# MCU_newPins.net
KiCad netlist of a schematic drawn in Altium Designer
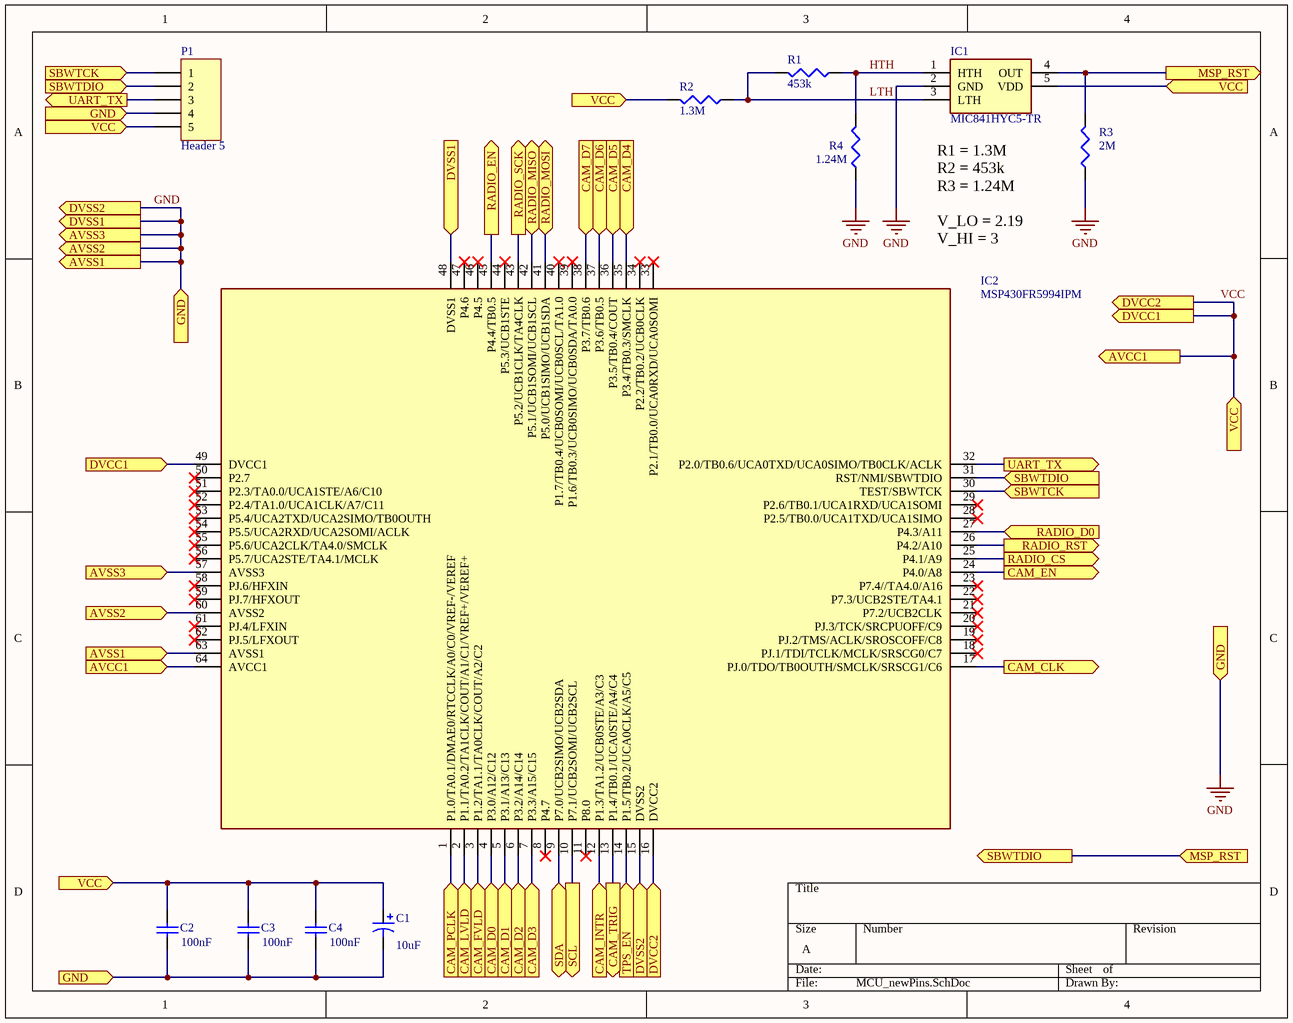
[diagram p0: MCU_newPins.SchDoc]

(export (version "E")
  (design (tool "Eeschema 10.0.6"))
  (components
    (comp (ref "C1")
      (value "10uF")
      (footprint "C1210")
      (description "Polarized Capacitor (Surface Mount)")
      (fields (field (name "PUBLISHER") "Altium Limited"))
      (libsource (lib "Miscellaneous Devices") (part "Cap Pol3"))
    )
    (comp (ref "C2")
      (value "100nF")
      (footprint "1608[0603]")
      (description "CAP CER 6.3V X5R/X7R 0603")
      (fields (field (name "Comment") "Cap") (field (name "PUBLISHER") "Altium Limited"))
      (libsource (lib "Miscellaneous Devices") (part "Cap"))
    )
    (comp (ref "C3")
      (value "100nF")
      (footprint "1608[0603]")
      (description "CAP CER 6.3V X5R/X7R 0603")
      (fields (field (name "Comment") "Cap") (field (name "PUBLISHER") "Altium Limited"))
      (libsource (lib "Miscellaneous Devices") (part "Cap"))
    )
    (comp (ref "C4")
      (value "100nF")
      (footprint "1608[0603]")
      (description "CAP CER 6.3V X5R/X7R 0603")
      (fields (field (name "Comment") "Cap") (field (name "PUBLISHER") "Altium Limited"))
      (libsource (lib "Miscellaneous Devices") (part "Cap"))
    )
    (comp (ref "IC1")
      (value "MIC841HYC5-TR")
      (footprint "SamacSys:SOT65P210X110-5N")
      (description "Comparator with 1.25% Reference and Adjustable Hysteresis")
      (fields
        (field (name "MOUSER PART NUMBER") "998-MIC841HYC5TR")
        (field (name "RS PART NUMBER") "1654292")
      )
      (libsource (lib "*") (part "MIC841HYC5-TR"))
    )
    (comp (ref "IC2")
      (value "MSP430FR5994IPM")
      (footprint "SamacSys:QFP50P1200X1200X160-64N")
      (description "Integrated Circuit")
      (fields (field (name "MOUSER PART NUMBER") "595-MSP430FR5994IPM"))
      (libsource (lib "*") (part "MSP430FR5994IPM"))
    )
    (comp (ref "P1")
      (value "Header 5")
      (footprint "MHDR1X5")
      (description "Header, 5-Pin")
      (fields (field (name "PUBLISHER") "Altium Limited"))
      (libsource (lib "Miscellaneous Connectors") (part "Header 5"))
    )
    (comp (ref "R1")
      (value "453k")
      (footprint "1608[0603]")
      (description "RES 1/10W 1% 0603 SMD")
      (fields (field (name "Comment") "Res3") (field (name "PUBLISHER") "Altium Limited"))
      (libsource (lib "Miscellaneous Devices") (part "Res3"))
    )
    (comp (ref "R2")
      (value "1.3M")
      (footprint "1608[0603]")
      (description "RES 1/10W 1% 0603 SMD")
      (fields (field (name "Comment") "Res3") (field (name "PUBLISHER") "Altium Limited"))
      (libsource (lib "Miscellaneous Devices") (part "Res3"))
    )
    (comp (ref "R3")
      (value "2M")
      (footprint "1608[0603]")
      (description "RES 1/10W 1% 0603 SMD")
      (fields (field (name "Comment") "Res3") (field (name "PUBLISHER") "Altium Limited"))
      (libsource (lib "Miscellaneous Devices") (part "Res3"))
    )
    (comp (ref "R4")
      (value "1.24M")
      (footprint "1608[0603]")
      (description "RES 1/10W 1% 0603 SMD")
      (fields (field (name "Comment") "Res3") (field (name "PUBLISHER") "Altium Limited"))
      (libsource (lib "Miscellaneous Devices") (part "Res3"))
    )
  )
  (nets
    (net (code "1") (name "/CAM_CLK") (class "Default")
      (node (ref "IC2") (pin "17") (pinfunction "PJ.0/TDO/TB0OUTH/SMCLK/SRSCG1/C6_17") (pintype "passive"))
    )
    (net (code "2") (name "/CAM_D0") (class "Default")
      (node (ref "IC2") (pin "4") (pinfunction "P3.0/A12/C12_4") (pintype "passive"))
    )
    (net (code "3") (name "/CAM_D1") (class "Default")
      (node (ref "IC2") (pin "5") (pinfunction "P3.1/A13/C13_5") (pintype "passive"))
    )
    (net (code "4") (name "/CAM_D2") (class "Default")
      (node (ref "IC2") (pin "6") (pinfunction "P3.2/A14/C14_6") (pintype "passive"))
    )
    (net (code "5") (name "/CAM_D3") (class "Default")
      (node (ref "IC2") (pin "7") (pinfunction "P3.3/A15/C15_7") (pintype "passive"))
    )
    (net (code "6") (name "/CAM_D4") (class "Default")
      (node (ref "IC2") (pin "35") (pinfunction "P3.4/TB0.3/SMCLK_35") (pintype "passive"))
    )
    (net (code "7") (name "/CAM_D5") (class "Default")
      (node (ref "IC2") (pin "36") (pinfunction "P3.5/TB0.4/COUT_36") (pintype "passive"))
    )
    (net (code "8") (name "/CAM_D6") (class "Default")
      (node (ref "IC2") (pin "37") (pinfunction "P3.6/TB0.5_37") (pintype "passive"))
    )
    (net (code "9") (name "/CAM_D7") (class "Default")
      (node (ref "IC2") (pin "38") (pinfunction "P3.7/TB0.6_38") (pintype "passive"))
    )
    (net (code "10") (name "/CAM_EN") (class "Default")
      (node (ref "IC2") (pin "24") (pinfunction "P4.0/A8_24") (pintype "passive"))
    )
    (net (code "11") (name "/CAM_FVLD") (class "Default")
      (node (ref "IC2") (pin "3") (pinfunction "P1.2/TA1.1/TA0CLK/COUT/A2/C2_3") (pintype "passive"))
    )
    (net (code "12") (name "/CAM_INTR") (class "Default")
      (node (ref "IC2") (pin "12") (pinfunction "P1.3/TA1.2/UCB0STE/A3/C3_12") (pintype "passive"))
    )
    (net (code "13") (name "/CAM_LVLD") (class "Default")
      (node (ref "IC2") (pin "2") (pinfunction "P1.1/TA0.2/TA1CLK/COUT/A1/C1/VREF+/VEREF+_2") (pintype "passive"))
    )
    (net (code "14") (name "/CAM_PCLK") (class "Default")
      (node (ref "IC2") (pin "1") (pinfunction "P1.0/TA0.1/DMAE0/RTCCLK/A0/C0/VREF-/VEREF_1") (pintype "passive"))
    )
    (net (code "15") (name "/CAM_TRIG") (class "Default")
      (node (ref "IC2") (pin "13") (pinfunction "P1.4/TB0.1/UCA0STE/A4/C4_13") (pintype "passive"))
    )
    (net (code "16") (name "/HTH") (class "Default")
      (node (ref "IC1") (pin "1") (pinfunction "HTH_1") (pintype "passive"))
      (node (ref "R1") (pin "1") (pinfunction "1_1") (pintype "passive"))
      (node (ref "R4") (pin "2") (pinfunction "2_2") (pintype "passive"))
    )
    (net (code "17") (name "/LTH") (class "Default")
      (node (ref "IC1") (pin "3") (pinfunction "LTH_3") (pintype "passive"))
      (node (ref "R1") (pin "2") (pinfunction "2_2") (pintype "passive"))
      (node (ref "R2") (pin "1") (pinfunction "1_1") (pintype "passive"))
    )
    (net (code "18") (name "/MSP_RST") (class "Default")
      (node (ref "IC1") (pin "4") (pinfunction "OUT_4") (pintype "passive"))
      (node (ref "IC2") (pin "31") (pinfunction "RST/NMI/SBWTDIO_31") (pintype "passive"))
      (node (ref "P1") (pin "2") (pinfunction "2_2") (pintype "passive"))
      (node (ref "R3") (pin "2") (pinfunction "2_2") (pintype "passive"))
    )
    (net (code "19") (name "/RADIO_CS") (class "Default")
      (node (ref "IC2") (pin "25") (pinfunction "P4.1/A9_25") (pintype "passive"))
    )
    (net (code "20") (name "/RADIO_D0") (class "Default")
      (node (ref "IC2") (pin "27") (pinfunction "P4.3/A11_27") (pintype "passive"))
    )
    (net (code "21") (name "/RADIO_EN") (class "Default")
      (node (ref "IC2") (pin "45") (pinfunction "P4.4/TB0.5_45") (pintype "passive"))
    )
    (net (code "22") (name "/RADIO_MISO") (class "Default")
      (node (ref "IC2") (pin "42") (pinfunction "P5.1/UCB1SOMI/UCB1SCL_42") (pintype "passive"))
    )
    (net (code "23") (name "/RADIO_MOSI") (class "Default")
      (node (ref "IC2") (pin "41") (pinfunction "P5.0/UCB1SIMO/UCB1SDA_41") (pintype "passive"))
    )
    (net (code "24") (name "/RADIO_RST") (class "Default")
      (node (ref "IC2") (pin "26") (pinfunction "P4.2/A10_26") (pintype "passive"))
    )
    (net (code "25") (name "/RADIO_SCK") (class "Default")
      (node (ref "IC2") (pin "43") (pinfunction "P5.2/UCB1CLK/TA4CLK_43") (pintype "passive"))
    )
    (net (code "26") (name "/SBWTCK") (class "Default")
      (node (ref "IC2") (pin "30") (pinfunction "TEST/SBWTCK_30") (pintype "passive"))
      (node (ref "P1") (pin "1") (pinfunction "1_1") (pintype "passive"))
    )
    (net (code "27") (name "/SCL") (class "Default")
      (node (ref "IC2") (pin "10") (pinfunction "P7.1/UCB2SOMI/UCB2SCL_10") (pintype "passive"))
    )
    (net (code "28") (name "/SDA") (class "Default")
      (node (ref "IC2") (pin "9") (pinfunction "P7.0/UCB2SIMO/UCB2SDA_9") (pintype "passive"))
    )
    (net (code "29") (name "/TPS_EN") (class "Default")
      (node (ref "IC2") (pin "14") (pinfunction "P1.5/TB0.2/UCA0CLK/A5/C5_14") (pintype "passive"))
    )
    (net (code "30") (name "/UART_TX") (class "Default")
      (node (ref "IC2") (pin "32") (pinfunction "P2.0/TB0.6/UCA0TXD/UCA0SIMO/TB0CLK/ACLK_32") (pintype "passive"))
      (node (ref "P1") (pin "3") (pinfunction "3_3") (pintype "passive"))
    )
    (net (code "31") (name "/VCC") (class "Default")
      (node (ref "C1") (pin "1") (pinfunction "1_1") (pintype "passive"))
      (node (ref "C2") (pin "2") (pinfunction "2_2") (pintype "passive"))
      (node (ref "C3") (pin "2") (pinfunction "2_2") (pintype "passive"))
      (node (ref "C4") (pin "2") (pinfunction "2_2") (pintype "passive"))
      (node (ref "IC1") (pin "5") (pinfunction "VDD_5") (pintype "passive"))
      (node (ref "IC2") (pin "16") (pinfunction "DVCC2_16") (pintype "passive"))
      (node (ref "IC2") (pin "49") (pinfunction "DVCC1_49") (pintype "passive"))
      (node (ref "IC2") (pin "64") (pinfunction "AVCC1_64") (pintype "passive"))
      (node (ref "P1") (pin "5") (pinfunction "5_5") (pintype "passive"))
      (node (ref "R2") (pin "2") (pinfunction "2_2") (pintype "passive"))
    )
    (net (code "32") (name "GND") (class "Default")
      (node (ref "C1") (pin "2") (pinfunction "2_2") (pintype "passive"))
      (node (ref "C2") (pin "1") (pinfunction "1_1") (pintype "passive"))
      (node (ref "C3") (pin "1") (pinfunction "1_1") (pintype "passive"))
      (node (ref "C4") (pin "1") (pinfunction "1_1") (pintype "passive"))
      (node (ref "IC1") (pin "2") (pinfunction "GND_2") (pintype "passive"))
      (node (ref "IC2") (pin "15") (pinfunction "DVSS2_15") (pintype "passive"))
      (node (ref "IC2") (pin "48") (pinfunction "DVSS1_48") (pintype "passive"))
      (node (ref "IC2") (pin "57") (pinfunction "AVSS3_57") (pintype "passive"))
      (node (ref "IC2") (pin "60") (pinfunction "AVSS2_60") (pintype "passive"))
      (node (ref "IC2") (pin "63") (pinfunction "AVSS1_63") (pintype "passive"))
      (node (ref "P1") (pin "4") (pinfunction "4_4") (pintype "passive"))
      (node (ref "R3") (pin "1") (pinfunction "1_1") (pintype "passive"))
      (node (ref "R4") (pin "1") (pinfunction "1_1") (pintype "passive"))
    )
    (net (code "33") (name "unconnected-(IC2-P1.6{slash}TB0.3{slash}UCB0SIMO{slash}UCB0SDA{slash}TA0.0-Pad39)") (class "Default")
      (node (ref "IC2") (pin "39") (pinfunction "P1.6/TB0.3/UCB0SIMO/UCB0SDA/TA0.0_39") (pintype "passive+no_connect"))
    )
    (net (code "34") (name "unconnected-(IC2-P1.7{slash}TB0.4{slash}UCB0SOMI{slash}UCB0SCL{slash}TA1.0-Pad40)") (class "Default")
      (node (ref "IC2") (pin "40") (pinfunction "P1.7/TB0.4/UCB0SOMI/UCB0SCL/TA1.0_40") (pintype "passive+no_connect"))
    )
    (net (code "35") (name "unconnected-(IC2-P2.1{slash}TB0.0{slash}UCA0RXD{slash}UCA0SOMI-Pad33)") (class "Default")
      (node (ref "IC2") (pin "33") (pinfunction "P2.1/TB0.0/UCA0RXD/UCA0SOMI_33") (pintype "passive+no_connect"))
    )
    (net (code "36") (name "unconnected-(IC2-P2.2{slash}TB0.2{slash}UCB0CLK-Pad34)") (class "Default")
      (node (ref "IC2") (pin "34") (pinfunction "P2.2/TB0.2/UCB0CLK_34") (pintype "passive+no_connect"))
    )
    (net (code "37") (name "unconnected-(IC2-P2.3{slash}TA0.0{slash}UCA1STE{slash}A6{slash}C10-Pad51)") (class "Default")
      (node (ref "IC2") (pin "51") (pinfunction "P2.3/TA0.0/UCA1STE/A6/C10_51") (pintype "passive+no_connect"))
    )
    (net (code "38") (name "unconnected-(IC2-P2.4{slash}TA1.0{slash}UCA1CLK{slash}A7{slash}C11-Pad52)") (class "Default")
      (node (ref "IC2") (pin "52") (pinfunction "P2.4/TA1.0/UCA1CLK/A7/C11_52") (pintype "passive+no_connect"))
    )
    (net (code "39") (name "unconnected-(IC2-P2.5{slash}TB0.0{slash}UCA1TXD{slash}UCA1SIMO-Pad28)") (class "Default")
      (node (ref "IC2") (pin "28") (pinfunction "P2.5/TB0.0/UCA1TXD/UCA1SIMO_28") (pintype "passive+no_connect"))
    )
    (net (code "40") (name "unconnected-(IC2-P2.6{slash}TB0.1{slash}UCA1RXD{slash}UCA1SOMI-Pad29)") (class "Default")
      (node (ref "IC2") (pin "29") (pinfunction "P2.6/TB0.1/UCA1RXD/UCA1SOMI_29") (pintype "passive+no_connect"))
    )
    (net (code "41") (name "unconnected-(IC2-P2.7-Pad50)") (class "Default")
      (node (ref "IC2") (pin "50") (pinfunction "P2.7_50") (pintype "passive+no_connect"))
    )
    (net (code "42") (name "unconnected-(IC2-P4.5-Pad46)") (class "Default")
      (node (ref "IC2") (pin "46") (pinfunction "P4.5_46") (pintype "passive+no_connect"))
    )
    (net (code "43") (name "unconnected-(IC2-P4.6-Pad47)") (class "Default")
      (node (ref "IC2") (pin "47") (pinfunction "P4.6_47") (pintype "passive+no_connect"))
    )
    (net (code "44") (name "unconnected-(IC2-P4.7-Pad8)") (class "Default")
      (node (ref "IC2") (pin "8") (pinfunction "P4.7_8") (pintype "passive+no_connect"))
    )
    (net (code "45") (name "unconnected-(IC2-P5.3{slash}UCB1STE-Pad44)") (class "Default")
      (node (ref "IC2") (pin "44") (pinfunction "P5.3/UCB1STE_44") (pintype "passive+no_connect"))
    )
    (net (code "46") (name "unconnected-(IC2-P5.4{slash}UCA2TXD{slash}UCA2SIMO{slash}TB0OUTH-Pad53)") (class "Default")
      (node (ref "IC2") (pin "53") (pinfunction "P5.4/UCA2TXD/UCA2SIMO/TB0OUTH_53") (pintype "passive+no_connect"))
    )
    (net (code "47") (name "unconnected-(IC2-P5.5{slash}UCA2RXD{slash}UCA2SOMI{slash}ACLK-Pad54)") (class "Default")
      (node (ref "IC2") (pin "54") (pinfunction "P5.5/UCA2RXD/UCA2SOMI/ACLK_54") (pintype "passive+no_connect"))
    )
    (net (code "48") (name "unconnected-(IC2-P5.6{slash}UCA2CLK{slash}TA4.0{slash}SMCLK-Pad55)") (class "Default")
      (node (ref "IC2") (pin "55") (pinfunction "P5.6/UCA2CLK/TA4.0/SMCLK_55") (pintype "passive+no_connect"))
    )
    (net (code "49") (name "unconnected-(IC2-P5.7{slash}UCA2STE{slash}TA4.1{slash}MCLK-Pad56)") (class "Default")
      (node (ref "IC2") (pin "56") (pinfunction "P5.7/UCA2STE/TA4.1/MCLK_56") (pintype "passive+no_connect"))
    )
    (net (code "50") (name "unconnected-(IC2-P7.2{slash}UCB2CLK-Pad21)") (class "Default")
      (node (ref "IC2") (pin "21") (pinfunction "P7.2/UCB2CLK_21") (pintype "passive+no_connect"))
    )
    (net (code "51") (name "unconnected-(IC2-P7.3{slash}UCB2STE{slash}TA4.1-Pad22)") (class "Default")
      (node (ref "IC2") (pin "22") (pinfunction "P7.3/UCB2STE/TA4.1_22") (pintype "passive+no_connect"))
    )
    (net (code "52") (name "unconnected-(IC2-P7.4{slash}{slash}TA4.0{slash}A16-Pad23)") (class "Default")
      (node (ref "IC2") (pin "23") (pinfunction "P7.4//TA4.0/A16_23") (pintype "passive+no_connect"))
    )
    (net (code "53") (name "unconnected-(IC2-P8.0-Pad11)") (class "Default")
      (node (ref "IC2") (pin "11") (pinfunction "P8.0_11") (pintype "passive+no_connect"))
    )
    (net (code "54") (name "unconnected-(IC2-PJ.1{slash}TDI{slash}TCLK{slash}MCLK{slash}SRSCG0{slash}C7-Pad18)") (class "Default")
      (node (ref "IC2") (pin "18") (pinfunction "PJ.1/TDI/TCLK/MCLK/SRSCG0/C7_18") (pintype "passive+no_connect"))
    )
    (net (code "55") (name "unconnected-(IC2-PJ.2{slash}TMS{slash}ACLK{slash}SROSCOFF{slash}C8-Pad19)") (class "Default")
      (node (ref "IC2") (pin "19") (pinfunction "PJ.2/TMS/ACLK/SROSCOFF/C8_19") (pintype "passive+no_connect"))
    )
    (net (code "56") (name "unconnected-(IC2-PJ.3{slash}TCK{slash}SRCPUOFF{slash}C9-Pad20)") (class "Default")
      (node (ref "IC2") (pin "20") (pinfunction "PJ.3/TCK/SRCPUOFF/C9_20") (pintype "passive+no_connect"))
    )
    (net (code "57") (name "unconnected-(IC2-PJ.4{slash}LFXIN-Pad61)") (class "Default")
      (node (ref "IC2") (pin "61") (pinfunction "PJ.4/LFXIN_61") (pintype "passive+no_connect"))
    )
    (net (code "58") (name "unconnected-(IC2-PJ.5{slash}LFXOUT-Pad62)") (class "Default")
      (node (ref "IC2") (pin "62") (pinfunction "PJ.5/LFXOUT_62") (pintype "passive+no_connect"))
    )
    (net (code "59") (name "unconnected-(IC2-PJ.6{slash}HFXIN-Pad58)") (class "Default")
      (node (ref "IC2") (pin "58") (pinfunction "PJ.6/HFXIN_58") (pintype "passive+no_connect"))
    )
    (net (code "60") (name "unconnected-(IC2-PJ.7{slash}HFXOUT-Pad59)") (class "Default")
      (node (ref "IC2") (pin "59") (pinfunction "PJ.7/HFXOUT_59") (pintype "passive+no_connect"))
    )
  )
)
